# LED_DRIVER.net
KiCad netlist of a schematic drawn in Altium Designer
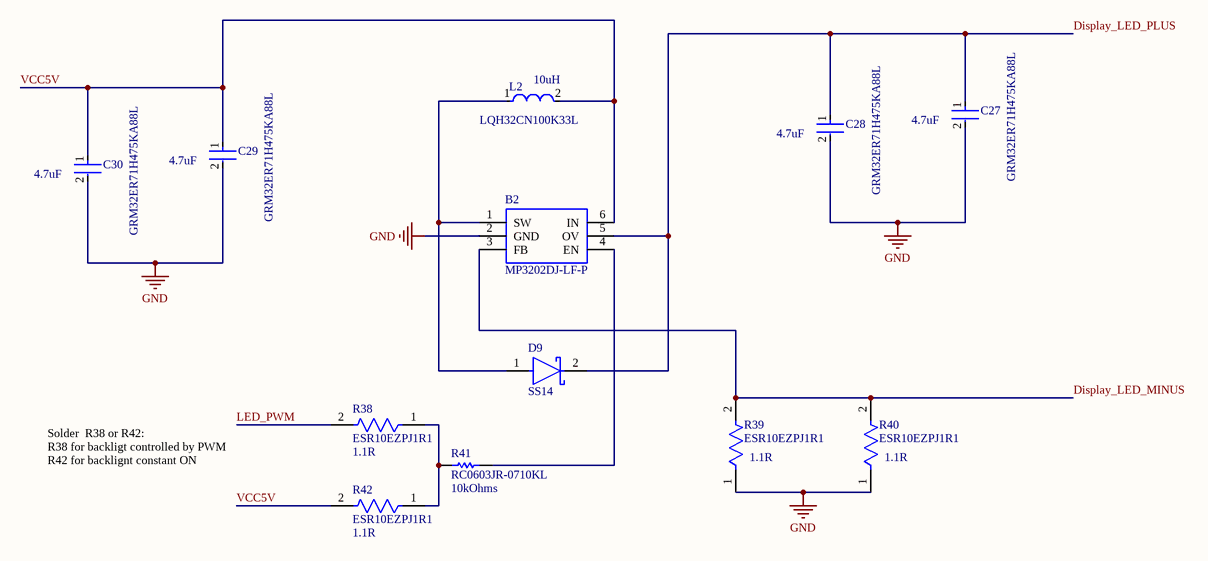
[diagram p0: LED_DRIVER.SchDoc]

(export (version "E")
  (design (tool "Eeschema 10.0.6"))
  (components
    (comp (ref "B2")
      (value "MP3202DJ-LF-P")
      (footprint "SOT95P280X100-6N")
      (description "Monolithic Power Systems (MPS) MP3202DJ-LF-P LED Driver IC, 2.5  6 V 6-Pin")
      (fields (field (name "MOUSER PART NUMBER") "946-MP3202DJLFP"))
      (libsource (lib "Schlib2") (part "MP3202DJ-LF-P"))
    )
    (comp (ref "C27")
      (value "GRM32ER71H475KA88L")
      (footprint "FP-GRM32-MFG")
      (description "CAP CER 4.7UF 50V X7R 1210")
      (fields
        (field (name "ALTIUM_VALUE") "4.7uF")
        (field (name "MANUFACTURER") "Murata")
        (field (name "TOLERANCE") "10%")
      )
      (libsource (lib "Altium Content Vault") (part "b4654b650e69147ec39a6b967a45e02"))
    )
    (comp (ref "C28")
      (value "GRM32ER71H475KA88L")
      (footprint "FP-GRM32-MFG")
      (description "CAP CER 4.7UF 50V X7R 1210")
      (fields
        (field (name "ALTIUM_VALUE") "4.7uF")
        (field (name "MANUFACTURER") "Murata")
        (field (name "TOLERANCE") "10%")
      )
      (libsource (lib "Altium Content Vault") (part "b4654b650e69147ec39a6b967a45e02"))
    )
    (comp (ref "C29")
      (value "GRM32ER71H475KA88L")
      (footprint "FP-GRM32-MFG")
      (description "CAP CER 4.7UF 50V X7R 1210")
      (fields
        (field (name "ALTIUM_VALUE") "4.7uF")
        (field (name "MANUFACTURER") "Murata")
        (field (name "TOLERANCE") "10%")
      )
      (libsource (lib "Altium Content Vault") (part "b4654b650e69147ec39a6b967a45e02"))
    )
    (comp (ref "C30")
      (value "GRM32ER71H475KA88L")
      (footprint "FP-GRM32-MFG")
      (description "CAP CER 4.7UF 50V X7R 1210")
      (fields
        (field (name "ALTIUM_VALUE") "4.7uF")
        (field (name "MANUFACTURER") "Murata")
        (field (name "TOLERANCE") "10%")
      )
      (libsource (lib "Altium Content Vault") (part "b4654b650e69147ec39a6b967a45e02"))
    )
    (comp (ref "D9")
      (value "SS14")
      (footprint "FP-403AE-MFG")
      (description "DIODE SCHOTTKY 40V 1A SMA")
      (fields
        (field (name "MANUFACTURER") "ON Semiconductor")
        (field (name "OCTOPART") "https://octopart.com/ss14-on+semiconductor-29205033")
      )
      (libsource (lib "Altium Content Vault") (part "360ad2f4ac25a952324d13796385471"))
    )
    (comp (ref "L2")
      (value "LQH32CN100K33L")
      (footprint "FP-LQH32CH_33-A2_3_2_8-MFG")
      (description "Wire Wound Ferrite Inductor for Power Lines 10μH ±10% 0.39Ω 450mA 1210")
      (fields (field (name "TOLERANCE") "10%") (field (name "INDUCTANCE") "10uH"))
      (libsource (lib "Altium Content Vault") (part "725321dda6339637d4d059423bc1c3c"))
    )
    (comp (ref "R38")
      (value "ESR10EZPJ1R1")
      (footprint "FP-ESR10-IPC_A")
      (description "1.1Ω ±5% 0.4W 0805 Anti-Surge Chip Resistor AEC-Q200")
      (fields (field (name "RESISTANCE") "1.1R") (field (name "TOLERANCE") "5%"))
      (libsource (lib "Altium Content Vault") (part "1029c3af85768c4190bb7ad29bc67b5"))
    )
    (comp (ref "R39")
      (value "ESR10EZPJ1R1")
      (footprint "FP-ESR10-IPC_A")
      (description "1.1Ω ±5% 0.4W 0805 Anti-Surge Chip Resistor AEC-Q200")
      (fields (field (name "RESISTANCE") "1.1R") (field (name "TOLERANCE") "5%"))
      (libsource (lib "Altium Content Vault") (part "1029c3af85768c4190bb7ad29bc67b5"))
    )
    (comp (ref "R40")
      (value "ESR10EZPJ1R1")
      (footprint "FP-ESR10-IPC_A")
      (description "1.1Ω ±5% 0.4W 0805 Anti-Surge Chip Resistor AEC-Q200")
      (fields (field (name "RESISTANCE") "1.1R") (field (name "TOLERANCE") "5%"))
      (libsource (lib "Altium Content Vault") (part "1029c3af85768c4190bb7ad29bc67b5"))
    )
    (comp (ref "R41")
      (value "RC0603JR-0710KL")
      (footprint "RESC1608X55X25ML10T15")
      (description "Resistor, 10 KOhm, +/- 5%, 100 mW, -55 to 155 degC, 0603 (1608 Metric), RoHS, Tape and Reel")
      (fields
        (field (name "RESISTANCE") "10kOhms")
        (field (name "MANUFACTURER") "Yageo")
        (field (name "TOLERANCE") "5%")
      )
      (libsource (lib "Altium Content Vault") (part "RES-2"))
    )
    (comp (ref "R42")
      (value "ESR10EZPJ1R1")
      (footprint "FP-ESR10-IPC_A")
      (description "1.1Ω ±5% 0.4W 0805 Anti-Surge Chip Resistor AEC-Q200")
      (fields (field (name "RESISTANCE") "1.1R") (field (name "TOLERANCE") "5%"))
      (libsource (lib "Altium Content Vault") (part "1029c3af85768c4190bb7ad29bc67b5"))
    )
  )
  (nets
    (net (code "1") (name "/Display_LED_MINUS") (class "Default")
      (node (ref "B2") (pin "3") (pinfunction "FB_3") (pintype "passive"))
      (node (ref "R39") (pin "2") (pinfunction "2_2") (pintype "passive"))
      (node (ref "R40") (pin "2") (pinfunction "2_2") (pintype "passive"))
    )
    (net (code "2") (name "/Display_LED_PLUS") (class "Default")
      (node (ref "B2") (pin "5") (pinfunction "OV_5") (pintype "passive"))
      (node (ref "C27") (pin "1") (pinfunction "1_1") (pintype "passive"))
      (node (ref "C28") (pin "1") (pinfunction "1_1") (pintype "passive"))
      (node (ref "D9") (pin "2") (pinfunction "C_2") (pintype "passive"))
    )
    (net (code "3") (name "/LED_PWM") (class "Default")
      (node (ref "R38") (pin "2") (pinfunction "2_2") (pintype "passive"))
    )
    (net (code "4") (name "/VCC5V") (class "Default")
      (node (ref "B2") (pin "6") (pinfunction "IN_6") (pintype "passive"))
      (node (ref "C29") (pin "1") (pinfunction "1_1") (pintype "passive"))
      (node (ref "C30") (pin "1") (pinfunction "1_1") (pintype "passive"))
      (node (ref "L2") (pin "2") (pinfunction "2_2") (pintype "passive"))
      (node (ref "R42") (pin "2") (pinfunction "2_2") (pintype "passive"))
    )
    (net (code "5") (name "GND") (class "Default")
      (node (ref "B2") (pin "2") (pinfunction "GND_2") (pintype "passive"))
      (node (ref "C27") (pin "2") (pinfunction "2_2") (pintype "passive"))
      (node (ref "C28") (pin "2") (pinfunction "2_2") (pintype "passive"))
      (node (ref "C29") (pin "2") (pinfunction "2_2") (pintype "passive"))
      (node (ref "C30") (pin "2") (pinfunction "2_2") (pintype "passive"))
      (node (ref "R39") (pin "1") (pinfunction "1_1") (pintype "passive"))
      (node (ref "R40") (pin "1") (pinfunction "1_1") (pintype "passive"))
    )
    (net (code "6") (name "Net-(B2-EN)") (class "Default")
      (node (ref "B2") (pin "4") (pinfunction "EN_4") (pintype "passive"))
      (node (ref "R41") (pin "1") (pinfunction "1_1") (pintype "passive"))
    )
    (net (code "7") (name "Net-(B2-SW)") (class "Default")
      (node (ref "B2") (pin "1") (pinfunction "SW_1") (pintype "passive"))
      (node (ref "D9") (pin "1") (pinfunction "A_1") (pintype "passive"))
      (node (ref "L2") (pin "1") (pinfunction "1_1") (pintype "passive"))
    )
    (net (code "8") (name "Net-(R38-Pad1)") (class "Default")
      (node (ref "R38") (pin "1") (pinfunction "1_1") (pintype "passive"))
      (node (ref "R41") (pin "2") (pinfunction "2_2") (pintype "passive"))
      (node (ref "R42") (pin "1") (pinfunction "1_1") (pintype "passive"))
    )
  )
)
